# sit_up_V2.net
KiCad netlist of a schematic drawn in EAGLE
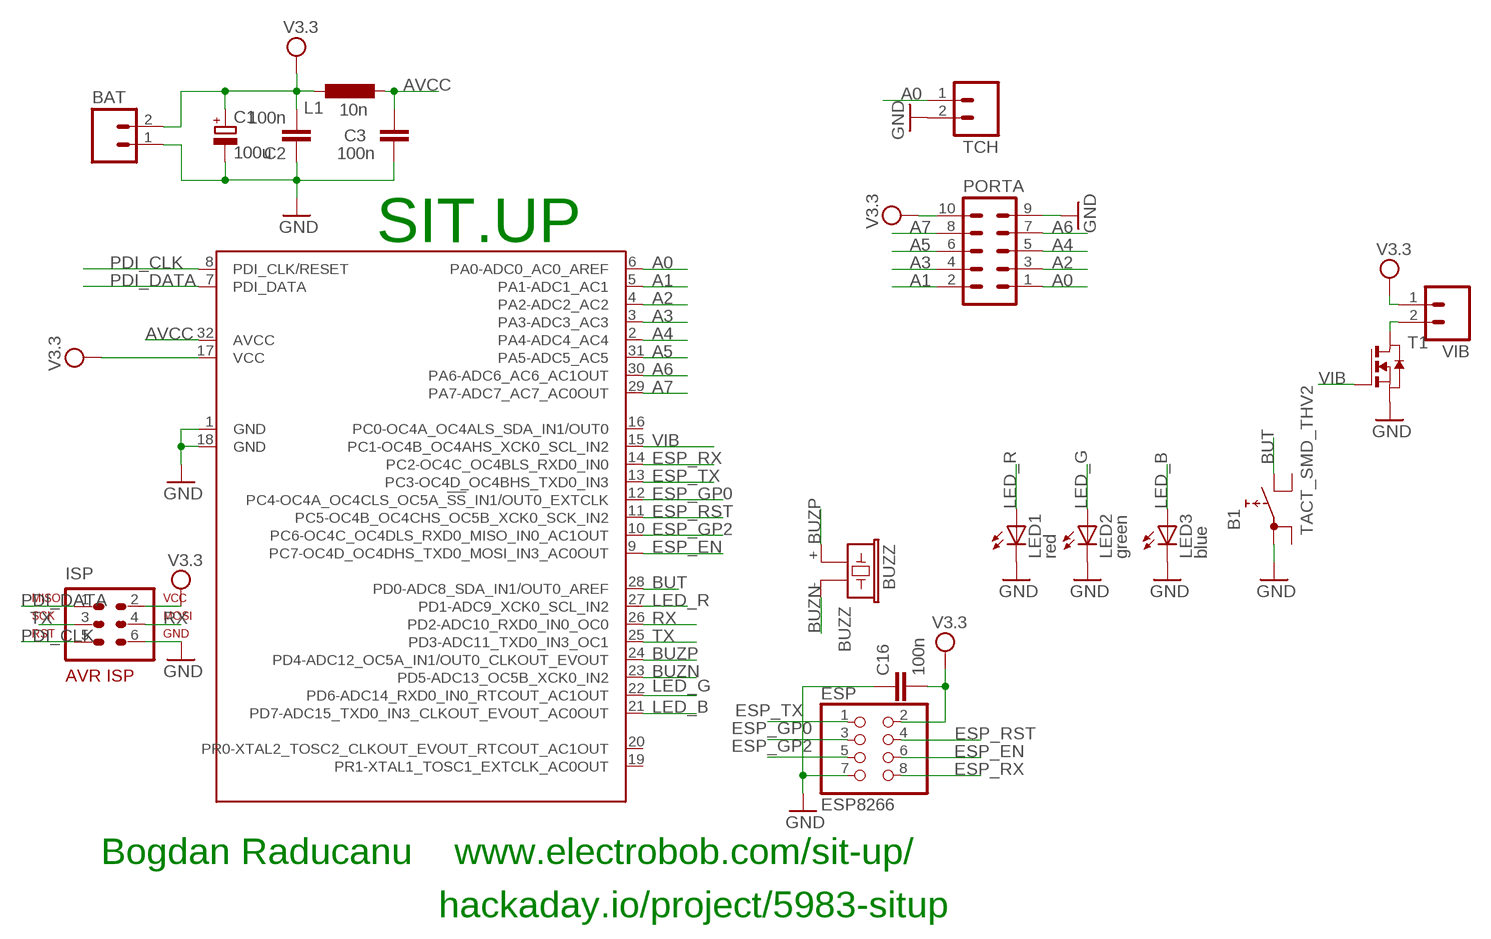
[diagram p0: schematic, sheet 1]

(export (version "E")
  (design (tool "Eeschema 10.0.6"))
  (components
    (comp (ref "B1")
      (value "TACT_SMD_THV2")
      (footprint "eagle-import:TACT_6MM_SMD_2")
      (libsource (lib "eagle-import") (part "TACT_SMD_THV2"))
    )
    (comp (ref "BAT")
      (value "M02")
      (footprint "eagle-import:02P")
      (libsource (lib "eagle-import") (part "M02"))
    )
    (comp (ref "BUZZ")
      (value "BUZZ")
      (footprint "eagle-import:F_CM12P")
      (libsource (lib "eagle-import") (part "F/CM12P"))
    )
    (comp (ref "C1")
      (value "100u")
      (footprint "eagle-import:153CLV-0505")
      (libsource (lib "eagle-import") (part "CPOL-EU153CLV-0505"))
    )
    (comp (ref "C2")
      (value "100n")
      (footprint "eagle-import:C0805")
      (libsource (lib "eagle-import") (part "C-EUC0805"))
    )
    (comp (ref "C3")
      (value "100n")
      (footprint "eagle-import:C0805")
      (libsource (lib "eagle-import") (part "C-EUC0805"))
    )
    (comp (ref "C16")
      (value "100n")
      (footprint "eagle-import:C0805")
      (libsource (lib "eagle-import") (part "C-EUC0805"))
    )
    (comp (ref "ESP")
      (value "ESP8266")
      (footprint "eagle-import:2X04")
      (libsource (lib "eagle-import") (part "PINHD-2X4"))
    )
    (comp (ref "ISP")
      (value "AVR-ISP-6VERT")
      (footprint "eagle-import:AVR-ISP-6")
      (libsource (lib "eagle-import") (part "AVR-ISP-6VERT"))
    )
    (comp (ref "L1")
      (value "10n")
      (footprint "eagle-import:L2012C")
      (libsource (lib "eagle-import") (part "L-EUL2012C"))
    )
    (comp (ref "LED1")
      (value "red")
      (footprint "eagle-import:LED3MM")
      (libsource (lib "eagle-import") (part "LED3MM"))
    )
    (comp (ref "LED2")
      (value "green")
      (footprint "eagle-import:LED3MM")
      (libsource (lib "eagle-import") (part "LED3MM"))
    )
    (comp (ref "LED3")
      (value "blue")
      (footprint "eagle-import:LED3MM")
      (libsource (lib "eagle-import") (part "LED3MM"))
    )
    (comp (ref "PORTA")
      (value "MA05-2_PORT")
      (footprint "eagle-import:MA05_PORT")
      (libsource (lib "eagle-import") (part "MA05-2_PORT"))
    )
    (comp (ref "T1")
      (value "NMOSSOT23")
      (footprint "eagle-import:SOT-23")
      (libsource (lib "eagle-import") (part "NMOSSOT23"))
    )
    (comp (ref "TCH")
      (value "M02")
      (footprint "eagle-import:02P")
      (libsource (lib "eagle-import") (part "M02"))
    )
    (comp (ref "VIB")
      (value "M02")
      (footprint "eagle-import:02P")
      (libsource (lib "eagle-import") (part "M02"))
    )
    (comp (ref "XMEGA")
      (value "XMEGA")
      (footprint "eagle-import:TQFP32")
      (libsource (lib "eagle-import") (part "E5-TQFP"))
    )
  )
  (nets
    (net (code "1") (name "/A0") (class "Default")
      (node (ref "PORTA") (pin "1") (pinfunction "1_1") (pintype "passive"))
      (node (ref "TCH") (pin "1") (pinfunction "1_1") (pintype "passive"))
      (node (ref "XMEGA") (pin "6") (pinfunction "PA0-ADC0_AC0_AREF_6") (pintype "bidirectional"))
    )
    (net (code "2") (name "/A1") (class "Default")
      (node (ref "PORTA") (pin "2") (pinfunction "2_2") (pintype "passive"))
      (node (ref "XMEGA") (pin "5") (pinfunction "PA1-ADC1_AC1_5") (pintype "bidirectional"))
    )
    (net (code "3") (name "/A2") (class "Default")
      (node (ref "PORTA") (pin "3") (pinfunction "3_3") (pintype "passive"))
      (node (ref "XMEGA") (pin "4") (pinfunction "PA2-ADC2_AC2_4") (pintype "bidirectional"))
    )
    (net (code "4") (name "/A3") (class "Default")
      (node (ref "PORTA") (pin "4") (pinfunction "4_4") (pintype "passive"))
      (node (ref "XMEGA") (pin "3") (pinfunction "PA3-ADC3_AC3_3") (pintype "bidirectional"))
    )
    (net (code "5") (name "/A4") (class "Default")
      (node (ref "PORTA") (pin "5") (pinfunction "5_5") (pintype "passive"))
      (node (ref "XMEGA") (pin "2") (pinfunction "PA4-ADC4_AC4_2") (pintype "bidirectional"))
    )
    (net (code "6") (name "/A5") (class "Default")
      (node (ref "PORTA") (pin "6") (pinfunction "6_6") (pintype "passive"))
      (node (ref "XMEGA") (pin "31") (pinfunction "PA5-ADC5_AC5_31") (pintype "bidirectional"))
    )
    (net (code "7") (name "/A6") (class "Default")
      (node (ref "PORTA") (pin "7") (pinfunction "7_7") (pintype "passive"))
      (node (ref "XMEGA") (pin "30") (pinfunction "PA6-ADC6_AC6_AC1OUT_30") (pintype "bidirectional"))
    )
    (net (code "8") (name "/A7") (class "Default")
      (node (ref "PORTA") (pin "8") (pinfunction "8_8") (pintype "passive"))
      (node (ref "XMEGA") (pin "29") (pinfunction "PA7-ADC7_AC7_AC0OUT_29") (pintype "bidirectional"))
    )
    (net (code "9") (name "/AVCC") (class "Default")
      (node (ref "C3") (pin "2") (pinfunction "2_2") (pintype "passive"))
      (node (ref "L1") (pin "2") (pinfunction "2_2") (pintype "passive"))
      (node (ref "XMEGA") (pin "32") (pinfunction "AVCC_32") (pintype "power_in"))
    )
    (net (code "10") (name "/BUT") (class "Default")
      (node (ref "B1") (pin "P$2") (pinfunction "2A_P$2") (pintype "passive"))
      (node (ref "XMEGA") (pin "28") (pinfunction "PD0-ADC8_SDA_IN1/OUT0_AREF_28") (pintype "bidirectional"))
    )
    (net (code "11") (name "/BUZN") (class "Default")
      (node (ref "BUZZ") (pin "-") (pinfunction "2_-") (pintype "passive"))
      (node (ref "XMEGA") (pin "23") (pinfunction "PD5-ADC13_OC5B_XCK0_IN2_23") (pintype "bidirectional"))
    )
    (net (code "12") (name "/BUZP") (class "Default")
      (node (ref "BUZZ") (pin "+") (pinfunction "1_+") (pintype "passive"))
      (node (ref "XMEGA") (pin "24") (pinfunction "PD4-ADC12_OC5A_IN1/OUT0_CLKOUT_EVOUT_24") (pintype "bidirectional"))
    )
    (net (code "13") (name "/ESP_EN") (class "Default")
      (node (ref "ESP") (pin "6") (pinfunction "6_6") (pintype "passive"))
      (node (ref "XMEGA") (pin "9") (pinfunction "PC7-OC4D_OC4DHS_TXD0_MOSI_IN3_AC0OUT_9") (pintype "bidirectional"))
    )
    (net (code "14") (name "/ESP_GP0") (class "Default")
      (node (ref "ESP") (pin "3") (pinfunction "3_3") (pintype "passive"))
      (node (ref "XMEGA") (pin "12") (pinfunction "PC4-OC4A_OC4CLS_OC5A_~{SS}_IN1/OUT0_EXTCLK_12") (pintype "bidirectional"))
    )
    (net (code "15") (name "/ESP_GP2") (class "Default")
      (node (ref "ESP") (pin "5") (pinfunction "5_5") (pintype "passive"))
      (node (ref "XMEGA") (pin "10") (pinfunction "PC6-OC4C_OC4DLS_RXD0_MISO_IN0_AC1OUT_10") (pintype "bidirectional"))
    )
    (net (code "16") (name "/ESP_RST") (class "Default")
      (node (ref "ESP") (pin "4") (pinfunction "4_4") (pintype "passive"))
      (node (ref "XMEGA") (pin "11") (pinfunction "PC5-OC4B_OC4CHS_OC5B_XCK0_SCK_IN2_11") (pintype "bidirectional"))
    )
    (net (code "17") (name "/ESP_RX") (class "Default")
      (node (ref "ESP") (pin "8") (pinfunction "8_8") (pintype "passive"))
      (node (ref "XMEGA") (pin "14") (pinfunction "PC2-OC4C_OC4BLS_RXD0_IN0_14") (pintype "bidirectional"))
    )
    (net (code "18") (name "/ESP_TX") (class "Default")
      (node (ref "ESP") (pin "1") (pinfunction "1_1") (pintype "passive"))
      (node (ref "XMEGA") (pin "13") (pinfunction "PC3-OC4D_OC4BHS_TXD0_IN3_13") (pintype "bidirectional"))
    )
    (net (code "19") (name "/LED_B") (class "Default")
      (node (ref "LED3") (pin "A") (pinfunction "A_A") (pintype "passive"))
      (node (ref "XMEGA") (pin "21") (pinfunction "PD7-ADC15_TXD0_IN3_CLKOUT_EVOUT_AC0OUT_21") (pintype "bidirectional"))
    )
    (net (code "20") (name "/LED_G") (class "Default")
      (node (ref "LED2") (pin "A") (pinfunction "A_A") (pintype "passive"))
      (node (ref "XMEGA") (pin "22") (pinfunction "PD6-ADC14_RXD0_IN0_RTCOUT_AC1OUT_22") (pintype "bidirectional"))
    )
    (net (code "21") (name "/LED_R") (class "Default")
      (node (ref "LED1") (pin "A") (pinfunction "A_A") (pintype "passive"))
      (node (ref "XMEGA") (pin "27") (pinfunction "PD1-ADC9_XCK0_SCL_IN2_27") (pintype "bidirectional"))
    )
    (net (code "22") (name "/PDI_CLK") (class "Default")
      (node (ref "ISP") (pin "5") (pinfunction "5_5") (pintype "passive"))
      (node (ref "XMEGA") (pin "8") (pinfunction "PDI_CLK/RESET_8") (pintype "bidirectional"))
    )
    (net (code "23") (name "/PDI_DATA") (class "Default")
      (node (ref "ISP") (pin "1") (pinfunction "1_1") (pintype "passive"))
      (node (ref "XMEGA") (pin "7") (pinfunction "PDI_DATA_7") (pintype "bidirectional"))
    )
    (net (code "24") (name "/RX") (class "Default")
      (node (ref "ISP") (pin "4") (pinfunction "4_4") (pintype "passive"))
      (node (ref "XMEGA") (pin "26") (pinfunction "PD2-ADC10_RXD0_IN0_OC0_26") (pintype "bidirectional"))
    )
    (net (code "25") (name "/TX") (class "Default")
      (node (ref "ISP") (pin "3") (pinfunction "3_3") (pintype "passive"))
      (node (ref "XMEGA") (pin "25") (pinfunction "PD3-ADC11_TXD0_IN3_OC1_25") (pintype "bidirectional"))
    )
    (net (code "26") (name "/VIB") (class "Default")
      (node (ref "T1") (pin "3") (pinfunction "G_3") (pintype "passive"))
      (node (ref "XMEGA") (pin "15") (pinfunction "PC1-OC4B_OC4AHS_XCK0_SCL_IN2_15") (pintype "bidirectional"))
    )
    (net (code "27") (name "GND") (class "Default")
      (node (ref "B1") (pin "P$1") (pinfunction "1A_P$1") (pintype "passive"))
      (node (ref "BAT") (pin "1") (pinfunction "1_1") (pintype "passive"))
      (node (ref "C1") (pin "-") (pinfunction "-_-") (pintype "passive"))
      (node (ref "C16") (pin "1") (pinfunction "1_1") (pintype "passive"))
      (node (ref "C2") (pin "1") (pinfunction "1_1") (pintype "passive"))
      (node (ref "C3") (pin "1") (pinfunction "1_1") (pintype "passive"))
      (node (ref "ESP") (pin "7") (pinfunction "7_7") (pintype "passive"))
      (node (ref "ISP") (pin "6") (pinfunction "6_6") (pintype "passive"))
      (node (ref "LED1") (pin "K") (pinfunction "C_K") (pintype "passive"))
      (node (ref "LED2") (pin "K") (pinfunction "C_K") (pintype "passive"))
      (node (ref "LED3") (pin "K") (pinfunction "C_K") (pintype "passive"))
      (node (ref "PORTA") (pin "9") (pinfunction "9_9") (pintype "passive"))
      (node (ref "T1") (pin "2") (pinfunction "S_2") (pintype "passive"))
      (node (ref "TCH") (pin "2") (pinfunction "2_2") (pintype "passive"))
      (node (ref "XMEGA") (pin "1") (pinfunction "GND_1") (pintype "power_in"))
      (node (ref "XMEGA") (pin "18") (pinfunction "GND_18") (pintype "power_in"))
    )
    (net (code "28") (name "Net-(T1-D)") (class "Default")
      (node (ref "T1") (pin "1") (pinfunction "D_1") (pintype "passive"))
      (node (ref "VIB") (pin "2") (pinfunction "2_2") (pintype "passive"))
    )
    (net (code "29") (name "V3.3") (class "Default")
      (node (ref "BAT") (pin "2") (pinfunction "2_2") (pintype "passive"))
      (node (ref "C1") (pin "+") (pinfunction "+_+") (pintype "passive"))
      (node (ref "C16") (pin "2") (pinfunction "2_2") (pintype "passive"))
      (node (ref "C2") (pin "2") (pinfunction "2_2") (pintype "passive"))
      (node (ref "ESP") (pin "2") (pinfunction "2_2") (pintype "passive"))
      (node (ref "ISP") (pin "2") (pinfunction "2_2") (pintype "passive"))
      (node (ref "L1") (pin "1") (pinfunction "1_1") (pintype "passive"))
      (node (ref "PORTA") (pin "10") (pinfunction "10_10") (pintype "passive"))
      (node (ref "VIB") (pin "1") (pinfunction "1_1") (pintype "passive"))
      (node (ref "XMEGA") (pin "17") (pinfunction "VCC_17") (pintype "power_in"))
    )
    (net (code "30") (name "unconnected-(B1-1B-PadP$3)") (class "Default")
      (node (ref "B1") (pin "P$3") (pinfunction "1B_P$3") (pintype "passive"))
    )
    (net (code "31") (name "unconnected-(B1-2B-PadP$4)") (class "Default")
      (node (ref "B1") (pin "P$4") (pinfunction "2B_P$4") (pintype "passive"))
    )
    (net (code "32") (name "unconnected-(XMEGA-PC0-OC4A_OC4ALS_SDA_IN1{slash}OUT0-Pad16)") (class "Default")
      (node (ref "XMEGA") (pin "16") (pinfunction "PC0-OC4A_OC4ALS_SDA_IN1/OUT0_16") (pintype "bidirectional"))
    )
    (net (code "33") (name "unconnected-(XMEGA-PR0-XTAL2_TOSC2_CLKOUT_EVOUT_RTCOUT_AC1OUT-Pad20)") (class "Default")
      (node (ref "XMEGA") (pin "20") (pinfunction "PR0-XTAL2_TOSC2_CLKOUT_EVOUT_RTCOUT_AC1OUT_20") (pintype "bidirectional"))
    )
    (net (code "34") (name "unconnected-(XMEGA-PR1-XTAL1_TOSC1_EXTCLK_AC0OUT-Pad19)") (class "Default")
      (node (ref "XMEGA") (pin "19") (pinfunction "PR1-XTAL1_TOSC1_EXTCLK_AC0OUT_19") (pintype "bidirectional"))
    )
  )
)
